# USB_TTL_Adapter_V1_1.net
KiCad netlist of a schematic drawn in EAGLE
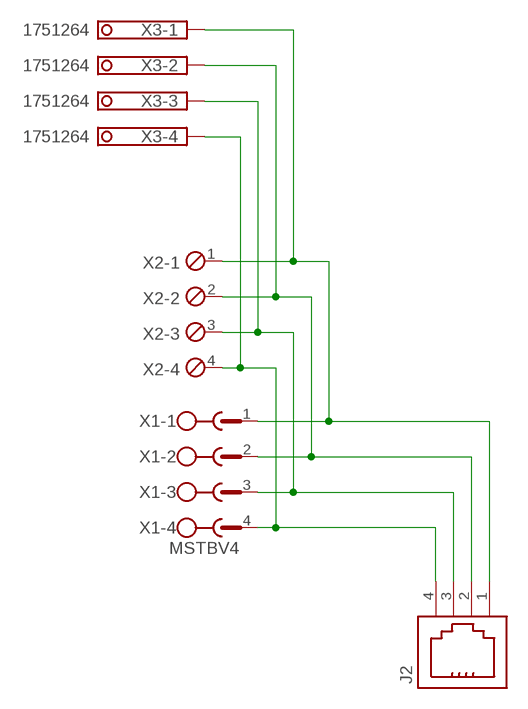
[diagram p0: schematic, sheet 1]

(export (version "E")
  (design (tool "Eeschema 10.0.6"))
  (components
    (comp (ref "J2")
      (value "615004144021")
      (footprint "eagle-import:615004144021")
      (libsource (lib "eagle-import") (part "615004144021"))
    )
    (comp (ref "X1")
      (value "MSTBV4")
      (footprint "eagle-import:MSTBV4")
      (fields (field (name "MPN") "MSTBV 2,5/4-GF-5.08"))
      (libsource (lib "eagle-import") (part "MSTBV4"))
    )
    (comp (ref "X2")
      (value "MPT4")
      (footprint "eagle-import:4POL254")
      (libsource (lib "eagle-import") (part "MPT4"))
    )
    (comp (ref "X3")
      (value "1751264")
      (footprint "eagle-import:1751264")
      (libsource (lib "eagle-import") (part "1751264"))
    )
  )
  (nets
    (net (code "1") (name "Net-(X1B-1)") (class "Default")
      (node (ref "J2") (pin "2") (pinfunction "2_2") (pintype "passive"))
      (node (ref "X1") (pin "2") (pinfunction "1_2") (pintype "passive"))
      (node (ref "X2") (pin "2") (pinfunction "1_2") (pintype "passive"))
      (node (ref "X3") (pin "2") (pinfunction "K_2") (pintype "passive"))
    )
    (net (code "2") (name "Net-(X1C-1)") (class "Default")
      (node (ref "J2") (pin "3") (pinfunction "3_3") (pintype "passive"))
      (node (ref "X1") (pin "3") (pinfunction "1_3") (pintype "passive"))
      (node (ref "X2") (pin "3") (pinfunction "1_3") (pintype "passive"))
      (node (ref "X3") (pin "3") (pinfunction "K_3") (pintype "passive"))
    )
    (net (code "3") (name "Net-(X1D-1)") (class "Default")
      (node (ref "J2") (pin "4") (pinfunction "4_4") (pintype "passive"))
      (node (ref "X1") (pin "4") (pinfunction "1_4") (pintype "passive"))
      (node (ref "X2") (pin "4") (pinfunction "1_4") (pintype "passive"))
      (node (ref "X3") (pin "4") (pinfunction "K_4") (pintype "passive"))
    )
    (net (code "4") (name "Net-(X3A-K)") (class "Default")
      (node (ref "J2") (pin "1") (pinfunction "1_1") (pintype "passive"))
      (node (ref "X1") (pin "1") (pinfunction "1_1") (pintype "passive"))
      (node (ref "X2") (pin "1") (pinfunction "1_1") (pintype "passive"))
      (node (ref "X3") (pin "1") (pinfunction "K_1") (pintype "passive"))
    )
  )
)
